# goodthopter10.net
KiCad netlist of a schematic drawn in EAGLE
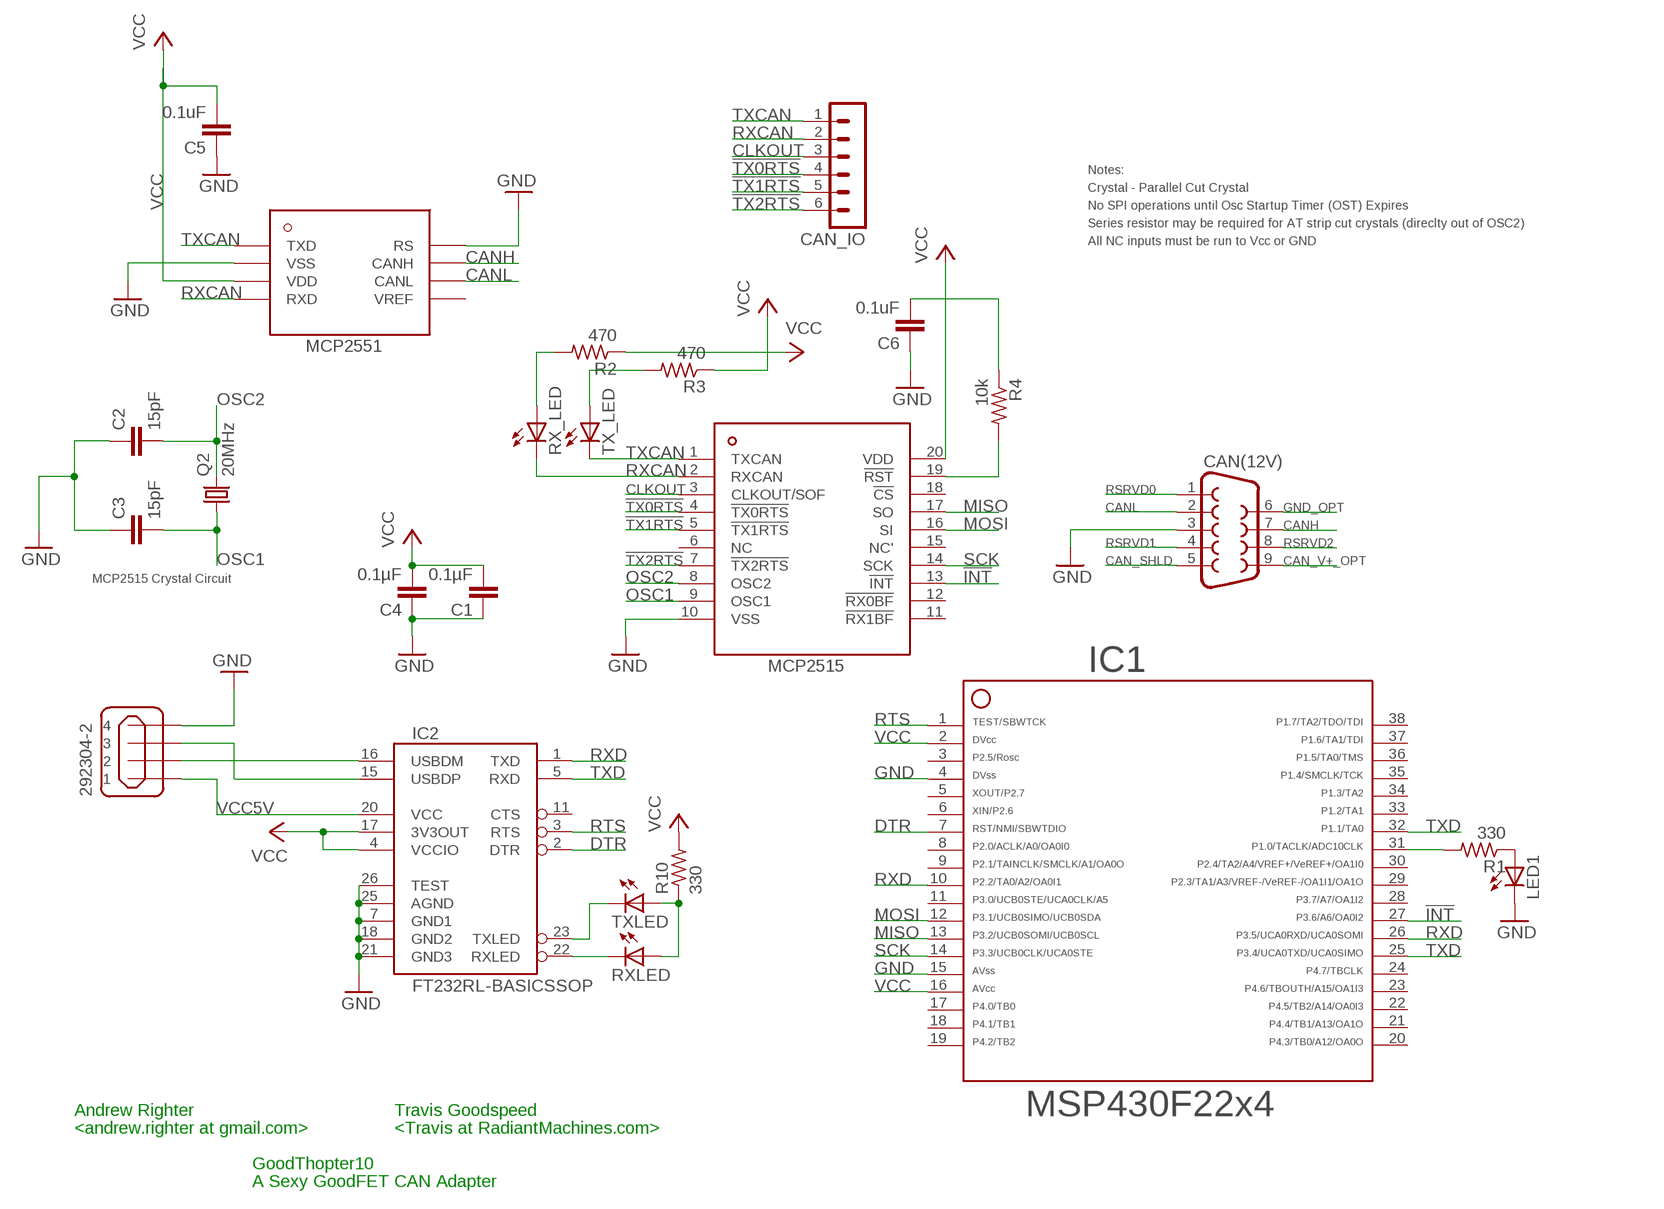
[diagram p0: schematic, sheet 1]

(export (version "E")
  (design (tool "Eeschema 10.0.6"))
  (components
    (comp (ref "292304-2")
      (value "MINI-USB_4P-292304-2")
      (footprint "eagle-import:85-32004-10X")
      (libsource (lib "eagle-import") (part "MINI-USB_4P-292304-2"))
    )
    (comp (ref "C1")
      (value "0.1µF")
      (footprint "eagle-import:C0603")
      (libsource (lib "eagle-import") (part "C-EUC0603"))
    )
    (comp (ref "C2")
      (value "15pF")
      (footprint "eagle-import:C0603")
      (libsource (lib "eagle-import") (part "C-EUC0603"))
    )
    (comp (ref "C3")
      (value "15pF")
      (footprint "eagle-import:C0603")
      (libsource (lib "eagle-import") (part "C-EUC0603"))
    )
    (comp (ref "C4")
      (value "0.1µF")
      (footprint "eagle-import:C0603")
      (libsource (lib "eagle-import") (part "C-EUC0603"))
    )
    (comp (ref "C5")
      (value "0.1uF")
      (footprint "eagle-import:C0603")
      (libsource (lib "eagle-import") (part "C-EUC0603"))
    )
    (comp (ref "C6")
      (value "0.1uF")
      (footprint "eagle-import:C0603")
      (libsource (lib "eagle-import") (part "C-EUC0603"))
    )
    (comp (ref "CAN(12V)")
      (value "DB9MALE")
      (footprint "eagle-import:DB9_MALE")
      (libsource (lib "eagle-import") (part "DB9MALE"))
    )
    (comp (ref "CAN_IO")
      (value "MA06-1")
      (footprint "eagle-import:MA06-1")
      (libsource (lib "eagle-import") (part "MA06-1"))
    )
    (comp (ref "IC1")
      (value "F22X4---DA38")
      (footprint "eagle-import:DA38")
      (libsource (lib "eagle-import") (part "F22X4---DA38"))
    )
    (comp (ref "IC2")
      (value "FT232RL-BASICSSOP")
      (footprint "eagle-import:SSOP28DB")
      (libsource (lib "eagle-import") (part "FT232RL-BASICSSOP"))
    )
    (comp (ref "LED1")
      (value "LEDCHIP-LED0603")
      (footprint "eagle-import:CHIP-LED0603")
      (libsource (lib "eagle-import") (part "LEDCHIP-LED0603"))
    )
    (comp (ref "Q2")
      (value "20MHz")
      (footprint "eagle-import:HC49UP")
      (libsource (lib "eagle-import") (part "CRYSTALHC49UP"))
    )
    (comp (ref "R1")
      (value "330")
      (footprint "eagle-import:R0603")
      (libsource (lib "eagle-import") (part "R-US_R0603"))
    )
    (comp (ref "R2")
      (value "470")
      (footprint "eagle-import:R0603")
      (libsource (lib "eagle-import") (part "R-US_R0603"))
    )
    (comp (ref "R3")
      (value "470")
      (footprint "eagle-import:R0603")
      (libsource (lib "eagle-import") (part "R-US_R0603"))
    )
    (comp (ref "R4")
      (value "10k")
      (footprint "eagle-import:R0603")
      (libsource (lib "eagle-import") (part "R-US_R0603"))
    )
    (comp (ref "R10")
      (value "330")
      (footprint "eagle-import:R0603")
      (libsource (lib "eagle-import") (part "R-US_R0603"))
    )
    (comp (ref "RXLED")
      (value "LEDCHIP-LED0603")
      (footprint "eagle-import:CHIP-LED0603")
      (libsource (lib "eagle-import") (part "LEDCHIP-LED0603"))
    )
    (comp (ref "RX_LED")
      (value "LEDCHIP-LED0603")
      (footprint "eagle-import:CHIP-LED0603")
      (libsource (lib "eagle-import") (part "LEDCHIP-LED0603"))
    )
    (comp (ref "TXLED")
      (value "LEDCHIP-LED0603")
      (footprint "eagle-import:CHIP-LED0603")
      (libsource (lib "eagle-import") (part "LEDCHIP-LED0603"))
    )
    (comp (ref "TX_LED")
      (value "LEDCHIP-LED0603")
      (footprint "eagle-import:CHIP-LED0603")
      (libsource (lib "eagle-import") (part "LEDCHIP-LED0603"))
    )
    (comp (ref "U$1")
      (value "MCP2515")
      (footprint "eagle-import:TSSOP20")
      (libsource (lib "eagle-import") (part "MCP2515"))
    )
    (comp (ref "U$2")
      (value "MCP2551")
      (footprint "eagle-import:SOIC-8")
      (libsource (lib "eagle-import") (part "MCP2551"))
    )
  )
  (nets
    (net (code "1") (name "/CANH") (class "Default")
      (node (ref "CAN(12V)") (pin "7") (pinfunction "7_7") (pintype "passive"))
      (node (ref "U$2") (pin "CANH") (pinfunction "CANH_CANH") (pintype "bidirectional"))
    )
    (net (code "2") (name "/CANL") (class "Default")
      (node (ref "CAN(12V)") (pin "2") (pinfunction "2_2") (pintype "passive"))
      (node (ref "U$2") (pin "CANL") (pinfunction "CANL_CANL") (pintype "bidirectional"))
    )
    (net (code "3") (name "/CAN_SHLD") (class "Default")
      (node (ref "CAN(12V)") (pin "5") (pinfunction "5_5") (pintype "passive"))
    )
    (net (code "4") (name "/CAN_V+_OPT") (class "Default")
      (node (ref "CAN(12V)") (pin "9") (pinfunction "9_9") (pintype "passive"))
    )
    (net (code "5") (name "/CLKOUT") (class "Default")
      (node (ref "CAN_IO") (pin "3") (pinfunction "3_3") (pintype "passive"))
      (node (ref "U$1") (pin "3") (pinfunction "CLKOUT/SOF_3") (pintype "bidirectional"))
    )
    (net (code "6") (name "/DTR") (class "Default")
      (node (ref "IC1") (pin "7") (pinfunction "7_7") (pintype "bidirectional"))
      (node (ref "IC2") (pin "2") (pinfunction "DTR_2") (pintype "bidirectional"))
    )
    (net (code "7") (name "/GND_OPT") (class "Default")
      (node (ref "CAN(12V)") (pin "6") (pinfunction "6_6") (pintype "passive"))
    )
    (net (code "8") (name "/MISO") (class "Default")
      (node (ref "IC1") (pin "13") (pinfunction "13_13") (pintype "bidirectional"))
      (node (ref "U$1") (pin "17") (pinfunction "SO_17") (pintype "bidirectional"))
    )
    (net (code "9") (name "/MOSI") (class "Default")
      (node (ref "IC1") (pin "12") (pinfunction "12_12") (pintype "bidirectional"))
      (node (ref "U$1") (pin "16") (pinfunction "SI_16") (pintype "bidirectional"))
    )
    (net (code "10") (name "/OSC1") (class "Default")
      (node (ref "C3") (pin "2") (pinfunction "2_2") (pintype "passive"))
      (node (ref "Q2") (pin "1") (pinfunction "1_1") (pintype "passive"))
      (node (ref "U$1") (pin "9") (pinfunction "OSC1_9") (pintype "bidirectional"))
    )
    (net (code "11") (name "/OSC2") (class "Default")
      (node (ref "C2") (pin "2") (pinfunction "2_2") (pintype "passive"))
      (node (ref "Q2") (pin "2") (pinfunction "2_2") (pintype "passive"))
      (node (ref "U$1") (pin "8") (pinfunction "OSC2_8") (pintype "bidirectional"))
    )
    (net (code "12") (name "/RSRVD0") (class "Default")
      (node (ref "CAN(12V)") (pin "1") (pinfunction "1_1") (pintype "passive"))
    )
    (net (code "13") (name "/RSRVD1") (class "Default")
      (node (ref "CAN(12V)") (pin "4") (pinfunction "4_4") (pintype "passive"))
    )
    (net (code "14") (name "/RSRVD2") (class "Default")
      (node (ref "CAN(12V)") (pin "8") (pinfunction "8_8") (pintype "passive"))
    )
    (net (code "15") (name "/RTS") (class "Default")
      (node (ref "IC1") (pin "1") (pinfunction "1_1") (pintype "input"))
      (node (ref "IC2") (pin "3") (pinfunction "RTS_3") (pintype "bidirectional"))
    )
    (net (code "16") (name "/RXCAN") (class "Default")
      (node (ref "CAN_IO") (pin "2") (pinfunction "2_2") (pintype "passive"))
      (node (ref "RX_LED") (pin "C") (pinfunction "C_C") (pintype "passive"))
      (node (ref "U$1") (pin "2") (pinfunction "RXCAN_2") (pintype "bidirectional"))
      (node (ref "U$2") (pin "RXD") (pinfunction "RXD_RXD") (pintype "bidirectional"))
    )
    (net (code "17") (name "/RXD") (class "Default")
      (node (ref "IC1") (pin "10") (pinfunction "10_10") (pintype "bidirectional"))
      (node (ref "IC1") (pin "26") (pinfunction "26_26") (pintype "bidirectional"))
      (node (ref "IC2") (pin "1") (pinfunction "TXD_1") (pintype "output"))
    )
    (net (code "18") (name "/SCK") (class "Default")
      (node (ref "IC1") (pin "14") (pinfunction "14_14") (pintype "bidirectional"))
      (node (ref "U$1") (pin "14") (pinfunction "SCK_14") (pintype "bidirectional"))
    )
    (net (code "19") (name "/TXCAN") (class "Default")
      (node (ref "CAN_IO") (pin "1") (pinfunction "1_1") (pintype "passive"))
      (node (ref "TX_LED") (pin "C") (pinfunction "C_C") (pintype "passive"))
      (node (ref "U$1") (pin "1") (pinfunction "TXCAN_1") (pintype "bidirectional"))
      (node (ref "U$2") (pin "TXD") (pinfunction "TXD_TXD") (pintype "bidirectional"))
    )
    (net (code "20") (name "/TXD") (class "Default")
      (node (ref "IC1") (pin "25") (pinfunction "25_25") (pintype "bidirectional"))
      (node (ref "IC1") (pin "32") (pinfunction "32_32") (pintype "bidirectional"))
      (node (ref "IC2") (pin "5") (pinfunction "RXD_5") (pintype "input"))
    )
    (net (code "21") (name "/VCC5V") (class "Default")
      (node (ref "292304-2") (pin "1") (pinfunction "1_1") (pintype "passive"))
      (node (ref "IC2") (pin "20") (pinfunction "VCC_20") (pintype "power_in"))
    )
    (net (code "22") (name "/~{INT}") (class "Default")
      (node (ref "IC1") (pin "27") (pinfunction "27_27") (pintype "bidirectional"))
      (node (ref "U$1") (pin "13") (pinfunction "~{INT}_13") (pintype "bidirectional"))
    )
    (net (code "23") (name "/~{TX0RTS}") (class "Default")
      (node (ref "CAN_IO") (pin "4") (pinfunction "4_4") (pintype "passive"))
      (node (ref "U$1") (pin "4") (pinfunction "~{TX0RTS}_4") (pintype "bidirectional"))
    )
    (net (code "24") (name "/~{TX1RTS}") (class "Default")
      (node (ref "CAN_IO") (pin "5") (pinfunction "5_5") (pintype "passive"))
      (node (ref "U$1") (pin "5") (pinfunction "~{TX1RTS}_5") (pintype "bidirectional"))
    )
    (net (code "25") (name "/~{TX2RTS}") (class "Default")
      (node (ref "CAN_IO") (pin "6") (pinfunction "6_6") (pintype "passive"))
      (node (ref "U$1") (pin "7") (pinfunction "~{TX2RTS}_7") (pintype "bidirectional"))
    )
    (net (code "26") (name "GND") (class "Default")
      (node (ref "292304-2") (pin "4") (pinfunction "4_4") (pintype "passive"))
      (node (ref "C1") (pin "1") (pinfunction "1_1") (pintype "passive"))
      (node (ref "C2") (pin "1") (pinfunction "1_1") (pintype "passive"))
      (node (ref "C3") (pin "1") (pinfunction "1_1") (pintype "passive"))
      (node (ref "C4") (pin "1") (pinfunction "1_1") (pintype "passive"))
      (node (ref "C5") (pin "1") (pinfunction "1_1") (pintype "passive"))
      (node (ref "C6") (pin "1") (pinfunction "1_1") (pintype "passive"))
      (node (ref "CAN(12V)") (pin "3") (pinfunction "3_3") (pintype "passive"))
      (node (ref "IC1") (pin "15") (pinfunction "15_15") (pintype "power_in"))
      (node (ref "IC1") (pin "4") (pinfunction "4_4") (pintype "power_in"))
      (node (ref "IC2") (pin "18") (pinfunction "GND2_18") (pintype "power_in"))
      (node (ref "IC2") (pin "21") (pinfunction "GND3_21") (pintype "power_in"))
      (node (ref "IC2") (pin "25") (pinfunction "AGND_25") (pintype "power_in"))
      (node (ref "IC2") (pin "26") (pinfunction "TEST_26") (pintype "input"))
      (node (ref "IC2") (pin "7") (pinfunction "GND1_7") (pintype "power_in"))
      (node (ref "LED1") (pin "C") (pinfunction "C_C") (pintype "passive"))
      (node (ref "U$1") (pin "10") (pinfunction "VSS_10") (pintype "bidirectional"))
      (node (ref "U$2") (pin "RS") (pinfunction "RS_RS") (pintype "bidirectional"))
      (node (ref "U$2") (pin "VSS") (pinfunction "VSS_VSS") (pintype "bidirectional"))
    )
    (net (code "27") (name "Net-(C6-Pad2)") (class "Default")
      (node (ref "C6") (pin "2") (pinfunction "2_2") (pintype "passive"))
      (node (ref "R4") (pin "1") (pinfunction "1_1") (pintype "passive"))
    )
    (net (code "28") (name "Net-(IC1-Pad31)") (class "Default")
      (node (ref "IC1") (pin "31") (pinfunction "31_31") (pintype "bidirectional"))
      (node (ref "R1") (pin "2") (pinfunction "2_2") (pintype "passive"))
    )
    (net (code "29") (name "Net-(IC2-RXLED)") (class "Default")
      (node (ref "IC2") (pin "22") (pinfunction "RXLED_22") (pintype "bidirectional"))
      (node (ref "RXLED") (pin "C") (pinfunction "C_C") (pintype "passive"))
    )
    (net (code "30") (name "Net-(IC2-TXLED)") (class "Default")
      (node (ref "IC2") (pin "23") (pinfunction "TXLED_23") (pintype "bidirectional"))
      (node (ref "TXLED") (pin "C") (pinfunction "C_C") (pintype "passive"))
    )
    (net (code "31") (name "Net-(IC2-USBDM)") (class "Default")
      (node (ref "292304-2") (pin "2") (pinfunction "2_2") (pintype "passive"))
      (node (ref "IC2") (pin "16") (pinfunction "USBDM_16") (pintype "bidirectional"))
    )
    (net (code "32") (name "Net-(IC2-USBDP)") (class "Default")
      (node (ref "292304-2") (pin "3") (pinfunction "3_3") (pintype "passive"))
      (node (ref "IC2") (pin "15") (pinfunction "USBDP_15") (pintype "bidirectional"))
    )
    (net (code "33") (name "Net-(LED1-PadA)") (class "Default")
      (node (ref "LED1") (pin "A") (pinfunction "A_A") (pintype "passive"))
      (node (ref "R1") (pin "1") (pinfunction "1_1") (pintype "passive"))
    )
    (net (code "34") (name "Net-(R2-Pad2)") (class "Default")
      (node (ref "R2") (pin "2") (pinfunction "2_2") (pintype "passive"))
      (node (ref "RX_LED") (pin "A") (pinfunction "A_A") (pintype "passive"))
    )
    (net (code "35") (name "Net-(R3-Pad2)") (class "Default")
      (node (ref "R3") (pin "2") (pinfunction "2_2") (pintype "passive"))
      (node (ref "TX_LED") (pin "A") (pinfunction "A_A") (pintype "passive"))
    )
    (net (code "36") (name "Net-(R10-Pad1)") (class "Default")
      (node (ref "R10") (pin "1") (pinfunction "1_1") (pintype "passive"))
      (node (ref "RXLED") (pin "A") (pinfunction "A_A") (pintype "passive"))
      (node (ref "TXLED") (pin "A") (pinfunction "A_A") (pintype "passive"))
    )
    (net (code "37") (name "Net-(U$1-~{RST})") (class "Default")
      (node (ref "R4") (pin "2") (pinfunction "2_2") (pintype "passive"))
      (node (ref "U$1") (pin "19") (pinfunction "~{RST}_19") (pintype "bidirectional"))
    )
    (net (code "38") (name "VCC") (class "Default")
      (node (ref "C1") (pin "2") (pinfunction "2_2") (pintype "passive"))
      (node (ref "C4") (pin "2") (pinfunction "2_2") (pintype "passive"))
      (node (ref "C5") (pin "2") (pinfunction "2_2") (pintype "passive"))
      (node (ref "IC1") (pin "16") (pinfunction "16_16") (pintype "power_in"))
      (node (ref "IC1") (pin "2") (pinfunction "2_2") (pintype "power_in"))
      (node (ref "IC2") (pin "17") (pinfunction "3V3OUT_17") (pintype "output"))
      (node (ref "IC2") (pin "4") (pinfunction "VCCIO_4") (pintype "power_in"))
      (node (ref "R10") (pin "2") (pinfunction "2_2") (pintype "passive"))
      (node (ref "R2") (pin "1") (pinfunction "1_1") (pintype "passive"))
      (node (ref "R3") (pin "1") (pinfunction "1_1") (pintype "passive"))
      (node (ref "U$1") (pin "20") (pinfunction "VDD_20") (pintype "bidirectional"))
      (node (ref "U$2") (pin "VDD") (pinfunction "VDD_VDD") (pintype "bidirectional"))
    )
    (net (code "39") (name "unconnected-(IC1-Pad3)") (class "Default")
      (node (ref "IC1") (pin "3") (pinfunction "3_3") (pintype "bidirectional"))
    )
    (net (code "40") (name "unconnected-(IC1-Pad5)") (class "Default")
      (node (ref "IC1") (pin "5") (pinfunction "5_5") (pintype "bidirectional"))
    )
    (net (code "41") (name "unconnected-(IC1-Pad6)") (class "Default")
      (node (ref "IC1") (pin "6") (pinfunction "6_6") (pintype "bidirectional"))
    )
    (net (code "42") (name "unconnected-(IC1-Pad8)") (class "Default")
      (node (ref "IC1") (pin "8") (pinfunction "8_8") (pintype "bidirectional"))
    )
    (net (code "43") (name "unconnected-(IC1-Pad9)") (class "Default")
      (node (ref "IC1") (pin "9") (pinfunction "9_9") (pintype "bidirectional"))
    )
    (net (code "44") (name "unconnected-(IC1-Pad11)") (class "Default")
      (node (ref "IC1") (pin "11") (pinfunction "11_11") (pintype "bidirectional"))
    )
    (net (code "45") (name "unconnected-(IC1-Pad17)") (class "Default")
      (node (ref "IC1") (pin "17") (pinfunction "17_17") (pintype "bidirectional"))
    )
    (net (code "46") (name "unconnected-(IC1-Pad18)") (class "Default")
      (node (ref "IC1") (pin "18") (pinfunction "18_18") (pintype "bidirectional"))
    )
    (net (code "47") (name "unconnected-(IC1-Pad19)") (class "Default")
      (node (ref "IC1") (pin "19") (pinfunction "19_19") (pintype "bidirectional"))
    )
    (net (code "48") (name "unconnected-(IC1-Pad20)") (class "Default")
      (node (ref "IC1") (pin "20") (pinfunction "20_20") (pintype "bidirectional"))
    )
    (net (code "49") (name "unconnected-(IC1-Pad21)") (class "Default")
      (node (ref "IC1") (pin "21") (pinfunction "21_21") (pintype "bidirectional"))
    )
    (net (code "50") (name "unconnected-(IC1-Pad22)") (class "Default")
      (node (ref "IC1") (pin "22") (pinfunction "22_22") (pintype "bidirectional"))
    )
    (net (code "51") (name "unconnected-(IC1-Pad23)") (class "Default")
      (node (ref "IC1") (pin "23") (pinfunction "23_23") (pintype "bidirectional"))
    )
    (net (code "52") (name "unconnected-(IC1-Pad24)") (class "Default")
      (node (ref "IC1") (pin "24") (pinfunction "24_24") (pintype "bidirectional"))
    )
    (net (code "53") (name "unconnected-(IC1-Pad28)") (class "Default")
      (node (ref "IC1") (pin "28") (pinfunction "28_28") (pintype "bidirectional"))
    )
    (net (code "54") (name "unconnected-(IC1-Pad29)") (class "Default")
      (node (ref "IC1") (pin "29") (pinfunction "29_29") (pintype "bidirectional"))
    )
    (net (code "55") (name "unconnected-(IC1-Pad30)") (class "Default")
      (node (ref "IC1") (pin "30") (pinfunction "30_30") (pintype "bidirectional"))
    )
    (net (code "56") (name "unconnected-(IC1-Pad33)") (class "Default")
      (node (ref "IC1") (pin "33") (pinfunction "33_33") (pintype "bidirectional"))
    )
    (net (code "57") (name "unconnected-(IC1-Pad34)") (class "Default")
      (node (ref "IC1") (pin "34") (pinfunction "34_34") (pintype "bidirectional"))
    )
    (net (code "58") (name "unconnected-(IC1-Pad35)") (class "Default")
      (node (ref "IC1") (pin "35") (pinfunction "35_35") (pintype "bidirectional"))
    )
    (net (code "59") (name "unconnected-(IC1-Pad36)") (class "Default")
      (node (ref "IC1") (pin "36") (pinfunction "36_36") (pintype "bidirectional"))
    )
    (net (code "60") (name "unconnected-(IC1-Pad37)") (class "Default")
      (node (ref "IC1") (pin "37") (pinfunction "37_37") (pintype "bidirectional"))
    )
    (net (code "61") (name "unconnected-(IC1-Pad38)") (class "Default")
      (node (ref "IC1") (pin "38") (pinfunction "38_38") (pintype "bidirectional"))
    )
    (net (code "62") (name "unconnected-(IC2-CTS-Pad11)") (class "Default")
      (node (ref "IC2") (pin "11") (pinfunction "CTS_11") (pintype "bidirectional"))
    )
    (net (code "63") (name "unconnected-(U$1-NC'-Pad15)") (class "Default")
      (node (ref "U$1") (pin "15") (pinfunction "NC'_15") (pintype "bidirectional"))
    )
    (net (code "64") (name "unconnected-(U$1-NC-Pad6)") (class "Default")
      (node (ref "U$1") (pin "6") (pinfunction "NC_6") (pintype "bidirectional"))
    )
    (net (code "65") (name "unconnected-(U$1-~{CS}-Pad18)") (class "Default")
      (node (ref "U$1") (pin "18") (pinfunction "~{CS}_18") (pintype "bidirectional"))
    )
    (net (code "66") (name "unconnected-(U$1-~{RX0BF}-Pad12)") (class "Default")
      (node (ref "U$1") (pin "12") (pinfunction "~{RX0BF}_12") (pintype "bidirectional"))
    )
    (net (code "67") (name "unconnected-(U$1-~{RX1BF}-Pad11)") (class "Default")
      (node (ref "U$1") (pin "11") (pinfunction "~{RX1BF}_11") (pintype "bidirectional"))
    )
    (net (code "68") (name "unconnected-(U$2-PadVREF)") (class "Default")
      (node (ref "U$2") (pin "VREF") (pinfunction "VREF_VREF") (pintype "bidirectional"))
    )
  )
)
